# wifi.net
KiCad netlist of a schematic drawn in Altium Designer
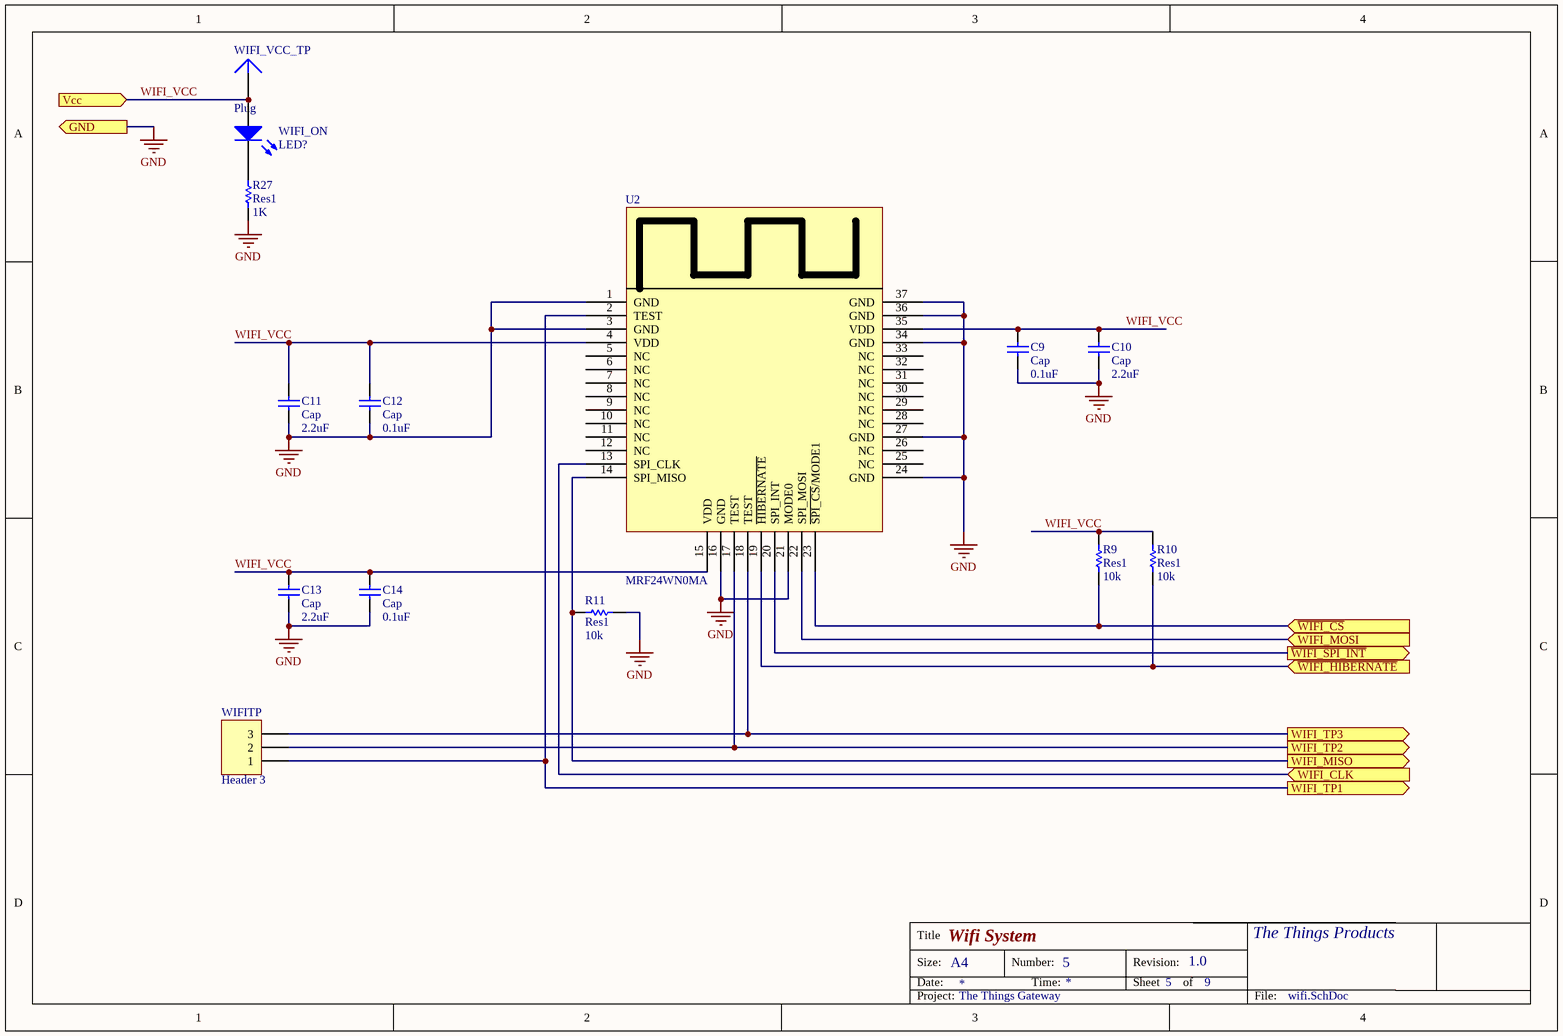
[diagram p0: wifi.SchDoc]

(export (version "E")
  (design (tool "Eeschema 10.0.6"))
  (components
    (comp (ref "C9")
      (value "Cap")
      (footprint "C0603")
      (description "Capacitor")
      (fields (field (name "ALTIUM_VALUE") "0.1uF") (field (name "PUBLISHER") "Altium Limited"))
      (libsource (lib "any") (part "Cap"))
    )
    (comp (ref "C10")
      (value "Cap")
      (footprint "C0603")
      (description "Capacitor")
      (fields (field (name "ALTIUM_VALUE") "2.2uF") (field (name "PUBLISHER") "Altium Limited"))
      (libsource (lib "any") (part "Cap"))
    )
    (comp (ref "C11")
      (value "Cap")
      (footprint "C0603")
      (description "Capacitor")
      (fields (field (name "ALTIUM_VALUE") "2.2uF") (field (name "PUBLISHER") "Altium Limited"))
      (libsource (lib "any") (part "Cap"))
    )
    (comp (ref "C12")
      (value "Cap")
      (footprint "C0603")
      (description "Capacitor")
      (fields (field (name "ALTIUM_VALUE") "0.1uF") (field (name "PUBLISHER") "Altium Limited"))
      (libsource (lib "any") (part "Cap"))
    )
    (comp (ref "C13")
      (value "Cap")
      (footprint "C0603")
      (description "Capacitor")
      (fields (field (name "ALTIUM_VALUE") "2.2uF") (field (name "PUBLISHER") "Altium Limited"))
      (libsource (lib "any") (part "Cap"))
    )
    (comp (ref "C14")
      (value "Cap")
      (footprint "C0603")
      (description "Capacitor")
      (fields (field (name "ALTIUM_VALUE") "0.1uF") (field (name "PUBLISHER") "Altium Limited"))
      (libsource (lib "any") (part "Cap"))
    )
    (comp (ref "R9")
      (value "Res1")
      (footprint "R0603")
      (description "Resistor")
      (fields (field (name "ALTIUM_VALUE") "10k") (field (name "PUBLISHER") "Altium Limited"))
      (libsource (lib "Miscellaneous Devices") (part "Res1"))
    )
    (comp (ref "R10")
      (value "Res1")
      (footprint "R0603")
      (description "Resistor")
      (fields (field (name "ALTIUM_VALUE") "10k") (field (name "PUBLISHER") "Altium Limited"))
      (libsource (lib "Miscellaneous Devices") (part "Res1"))
    )
    (comp (ref "R11")
      (value "Res1")
      (footprint "R0603")
      (description "Resistor")
      (fields (field (name "ALTIUM_VALUE") "10k") (field (name "PUBLISHER") "Altium Limited"))
      (libsource (lib "Miscellaneous Devices") (part "Res1"))
    )
    (comp (ref "R27")
      (value "Res1")
      (footprint "R0603")
      (description "Resistor")
      (fields (field (name "ALTIUM_VALUE") "1K") (field (name "PUBLISHER") "Altium Limited"))
      (libsource (lib "any") (part "Res1"))
    )
    (comp (ref "U2")
      (value "MRF24WN0MA")
      (footprint "MRF24WN0MA")
      (description "MRF24WN0MA Wifi SOC")
      (libsource (lib "ttn_schematic_library") (part "MRF24WN0MA"))
    )
    (comp (ref "WIFITP")
      (value "Header 3")
      (footprint "HDR1X3")
      (description "Header, 3-Pin")
      (fields (field (name "PUBLISHER") "Altium Limited"))
      (libsource (lib "Miscellaneous Connectors") (part "Header 3"))
    )
    (comp (ref "WIFI_ON")
      (value "LED?")
      (footprint "C0603")
      (description "Typical INFRARED GaAs LED")
      (fields (field (name "PUBLISHER") "Altium Limited"))
      (libsource (lib "any") (part "LED0"))
    )
    (comp (ref "WIFI_VCC_TP")
      (value "Plug")
      (footprint "PIN1")
      (fields (field (name "PUBLISHER") "Altium Limited"))
      (libsource (lib "Miscellaneous Connectors") (part "Plug"))
    )
  )
  (nets
    (net (code "1") (name "/WIFI_CLK") (class "Default")
      (node (ref "U2") (pin "13") (pinfunction "SPI_CLK_13") (pintype "passive"))
    )
    (net (code "2") (name "/WIFI_MISO") (class "Default")
      (node (ref "R11") (pin "2") (pinfunction "2_2") (pintype "passive"))
      (node (ref "U2") (pin "14") (pinfunction "SPI_MISO_14") (pintype "passive"))
    )
    (net (code "3") (name "/WIFI_MOSI") (class "Default")
      (node (ref "U2") (pin "22") (pinfunction "SPI_MOSI_22") (pintype "passive"))
    )
    (net (code "4") (name "/WIFI_TP1") (class "Default")
      (node (ref "U2") (pin "2") (pinfunction "TEST_2") (pintype "passive"))
      (node (ref "WIFITP") (pin "1") (pinfunction "1_1") (pintype "passive"))
    )
    (net (code "5") (name "/WIFI_TP2") (class "Default")
      (node (ref "U2") (pin "17") (pinfunction "TEST_17") (pintype "passive"))
      (node (ref "WIFITP") (pin "2") (pinfunction "2_2") (pintype "passive"))
    )
    (net (code "6") (name "/WIFI_TP3") (class "Default")
      (node (ref "U2") (pin "18") (pinfunction "TEST_18") (pintype "passive"))
      (node (ref "WIFITP") (pin "3") (pinfunction "3_3") (pintype "passive"))
    )
    (net (code "7") (name "/WIFI_VCC") (class "Default")
      (node (ref "C10") (pin "2") (pinfunction "2_2") (pintype "passive"))
      (node (ref "C11") (pin "2") (pinfunction "2_2") (pintype "passive"))
      (node (ref "C12") (pin "2") (pinfunction "2_2") (pintype "passive"))
      (node (ref "C13") (pin "2") (pinfunction "2_2") (pintype "passive"))
      (node (ref "C14") (pin "2") (pinfunction "2_2") (pintype "passive"))
      (node (ref "C9") (pin "2") (pinfunction "2_2") (pintype "passive"))
      (node (ref "R10") (pin "2") (pinfunction "2_2") (pintype "passive"))
      (node (ref "R9") (pin "2") (pinfunction "2_2") (pintype "passive"))
      (node (ref "U2") (pin "15") (pinfunction "VDD_15") (pintype "passive"))
      (node (ref "U2") (pin "35") (pinfunction "VDD_35") (pintype "passive"))
      (node (ref "U2") (pin "4") (pinfunction "VDD_4") (pintype "passive"))
      (node (ref "WIFI_ON") (pin "1") (pinfunction "A_1") (pintype "passive"))
      (node (ref "WIFI_VCC_TP") (pin "1") (pinfunction "1_1") (pintype "passive"))
    )
    (net (code "8") (name "/~{WIFI_CS}") (class "Default")
      (node (ref "R9") (pin "1") (pinfunction "1_1") (pintype "passive"))
      (node (ref "U2") (pin "23") (pinfunction "~{SPI_CS}/MODE1_23") (pintype "passive"))
    )
    (net (code "9") (name "/~{WIFI_HIBERNATE}") (class "Default")
      (node (ref "R10") (pin "1") (pinfunction "1_1") (pintype "passive"))
      (node (ref "U2") (pin "19") (pinfunction "~{HIBERNATE}_19") (pintype "passive"))
    )
    (net (code "10") (name "/~{WIFI_SPI_INT}") (class "Default")
      (node (ref "U2") (pin "20") (pinfunction "SPI_INT_20") (pintype "passive"))
    )
    (net (code "11") (name "GND") (class "Default")
      (node (ref "C10") (pin "1") (pinfunction "1_1") (pintype "passive"))
      (node (ref "C11") (pin "1") (pinfunction "1_1") (pintype "passive"))
      (node (ref "C12") (pin "1") (pinfunction "1_1") (pintype "passive"))
      (node (ref "C13") (pin "1") (pinfunction "1_1") (pintype "passive"))
      (node (ref "C14") (pin "1") (pinfunction "1_1") (pintype "passive"))
      (node (ref "C9") (pin "1") (pinfunction "1_1") (pintype "passive"))
      (node (ref "R11") (pin "1") (pinfunction "1_1") (pintype "passive"))
      (node (ref "R27") (pin "1") (pinfunction "1_1") (pintype "passive"))
      (node (ref "U2") (pin "1") (pinfunction "GND_1") (pintype "passive"))
      (node (ref "U2") (pin "16") (pinfunction "GND_16") (pintype "passive"))
      (node (ref "U2") (pin "21") (pinfunction "MODE0_21") (pintype "passive"))
      (node (ref "U2") (pin "24") (pinfunction "GND_24") (pintype "passive"))
      (node (ref "U2") (pin "27") (pinfunction "GND_27") (pintype "passive"))
      (node (ref "U2") (pin "3") (pinfunction "GND_3") (pintype "passive"))
      (node (ref "U2") (pin "34") (pinfunction "GND_34") (pintype "passive"))
      (node (ref "U2") (pin "36") (pinfunction "GND_36") (pintype "passive"))
      (node (ref "U2") (pin "37") (pinfunction "GND_37") (pintype "passive"))
    )
    (net (code "12") (name "Net-(WIFI_ON-K)") (class "Default")
      (node (ref "R27") (pin "2") (pinfunction "2_2") (pintype "passive"))
      (node (ref "WIFI_ON") (pin "2") (pinfunction "K_2") (pintype "passive"))
    )
    (net (code "13") (name "unconnected-(U2-NC-Pad5)") (class "Default")
      (node (ref "U2") (pin "5") (pinfunction "NC_5") (pintype "passive"))
    )
    (net (code "14") (name "unconnected-(U2-NC-Pad6)") (class "Default")
      (node (ref "U2") (pin "6") (pinfunction "NC_6") (pintype "passive"))
    )
    (net (code "15") (name "unconnected-(U2-NC-Pad7)") (class "Default")
      (node (ref "U2") (pin "7") (pinfunction "NC_7") (pintype "passive"))
    )
    (net (code "16") (name "unconnected-(U2-NC-Pad8)") (class "Default")
      (node (ref "U2") (pin "8") (pinfunction "NC_8") (pintype "passive"))
    )
    (net (code "17") (name "unconnected-(U2-NC-Pad9)") (class "Default")
      (node (ref "U2") (pin "9") (pinfunction "NC_9") (pintype "passive"))
    )
    (net (code "18") (name "unconnected-(U2-NC-Pad10)") (class "Default")
      (node (ref "U2") (pin "10") (pinfunction "NC_10") (pintype "passive"))
    )
    (net (code "19") (name "unconnected-(U2-NC-Pad11)") (class "Default")
      (node (ref "U2") (pin "11") (pinfunction "NC_11") (pintype "passive"))
    )
    (net (code "20") (name "unconnected-(U2-NC-Pad12)") (class "Default")
      (node (ref "U2") (pin "12") (pinfunction "NC_12") (pintype "passive"))
    )
    (net (code "21") (name "unconnected-(U2-NC-Pad25)") (class "Default")
      (node (ref "U2") (pin "25") (pinfunction "NC_25") (pintype "passive"))
    )
    (net (code "22") (name "unconnected-(U2-NC-Pad26)") (class "Default")
      (node (ref "U2") (pin "26") (pinfunction "NC_26") (pintype "passive"))
    )
    (net (code "23") (name "unconnected-(U2-NC-Pad28)") (class "Default")
      (node (ref "U2") (pin "28") (pinfunction "NC_28") (pintype "passive"))
    )
    (net (code "24") (name "unconnected-(U2-NC-Pad29)") (class "Default")
      (node (ref "U2") (pin "29") (pinfunction "NC_29") (pintype "passive"))
    )
    (net (code "25") (name "unconnected-(U2-NC-Pad30)") (class "Default")
      (node (ref "U2") (pin "30") (pinfunction "NC_30") (pintype "passive"))
    )
    (net (code "26") (name "unconnected-(U2-NC-Pad31)") (class "Default")
      (node (ref "U2") (pin "31") (pinfunction "NC_31") (pintype "passive"))
    )
    (net (code "27") (name "unconnected-(U2-NC-Pad32)") (class "Default")
      (node (ref "U2") (pin "32") (pinfunction "NC_32") (pintype "passive"))
    )
    (net (code "28") (name "unconnected-(U2-NC-Pad33)") (class "Default")
      (node (ref "U2") (pin "33") (pinfunction "NC_33") (pintype "passive"))
    )
  )
)
